# 2_waffling60-SE_matrix.net
KiCad netlist of a schematic drawn in Altium Designer
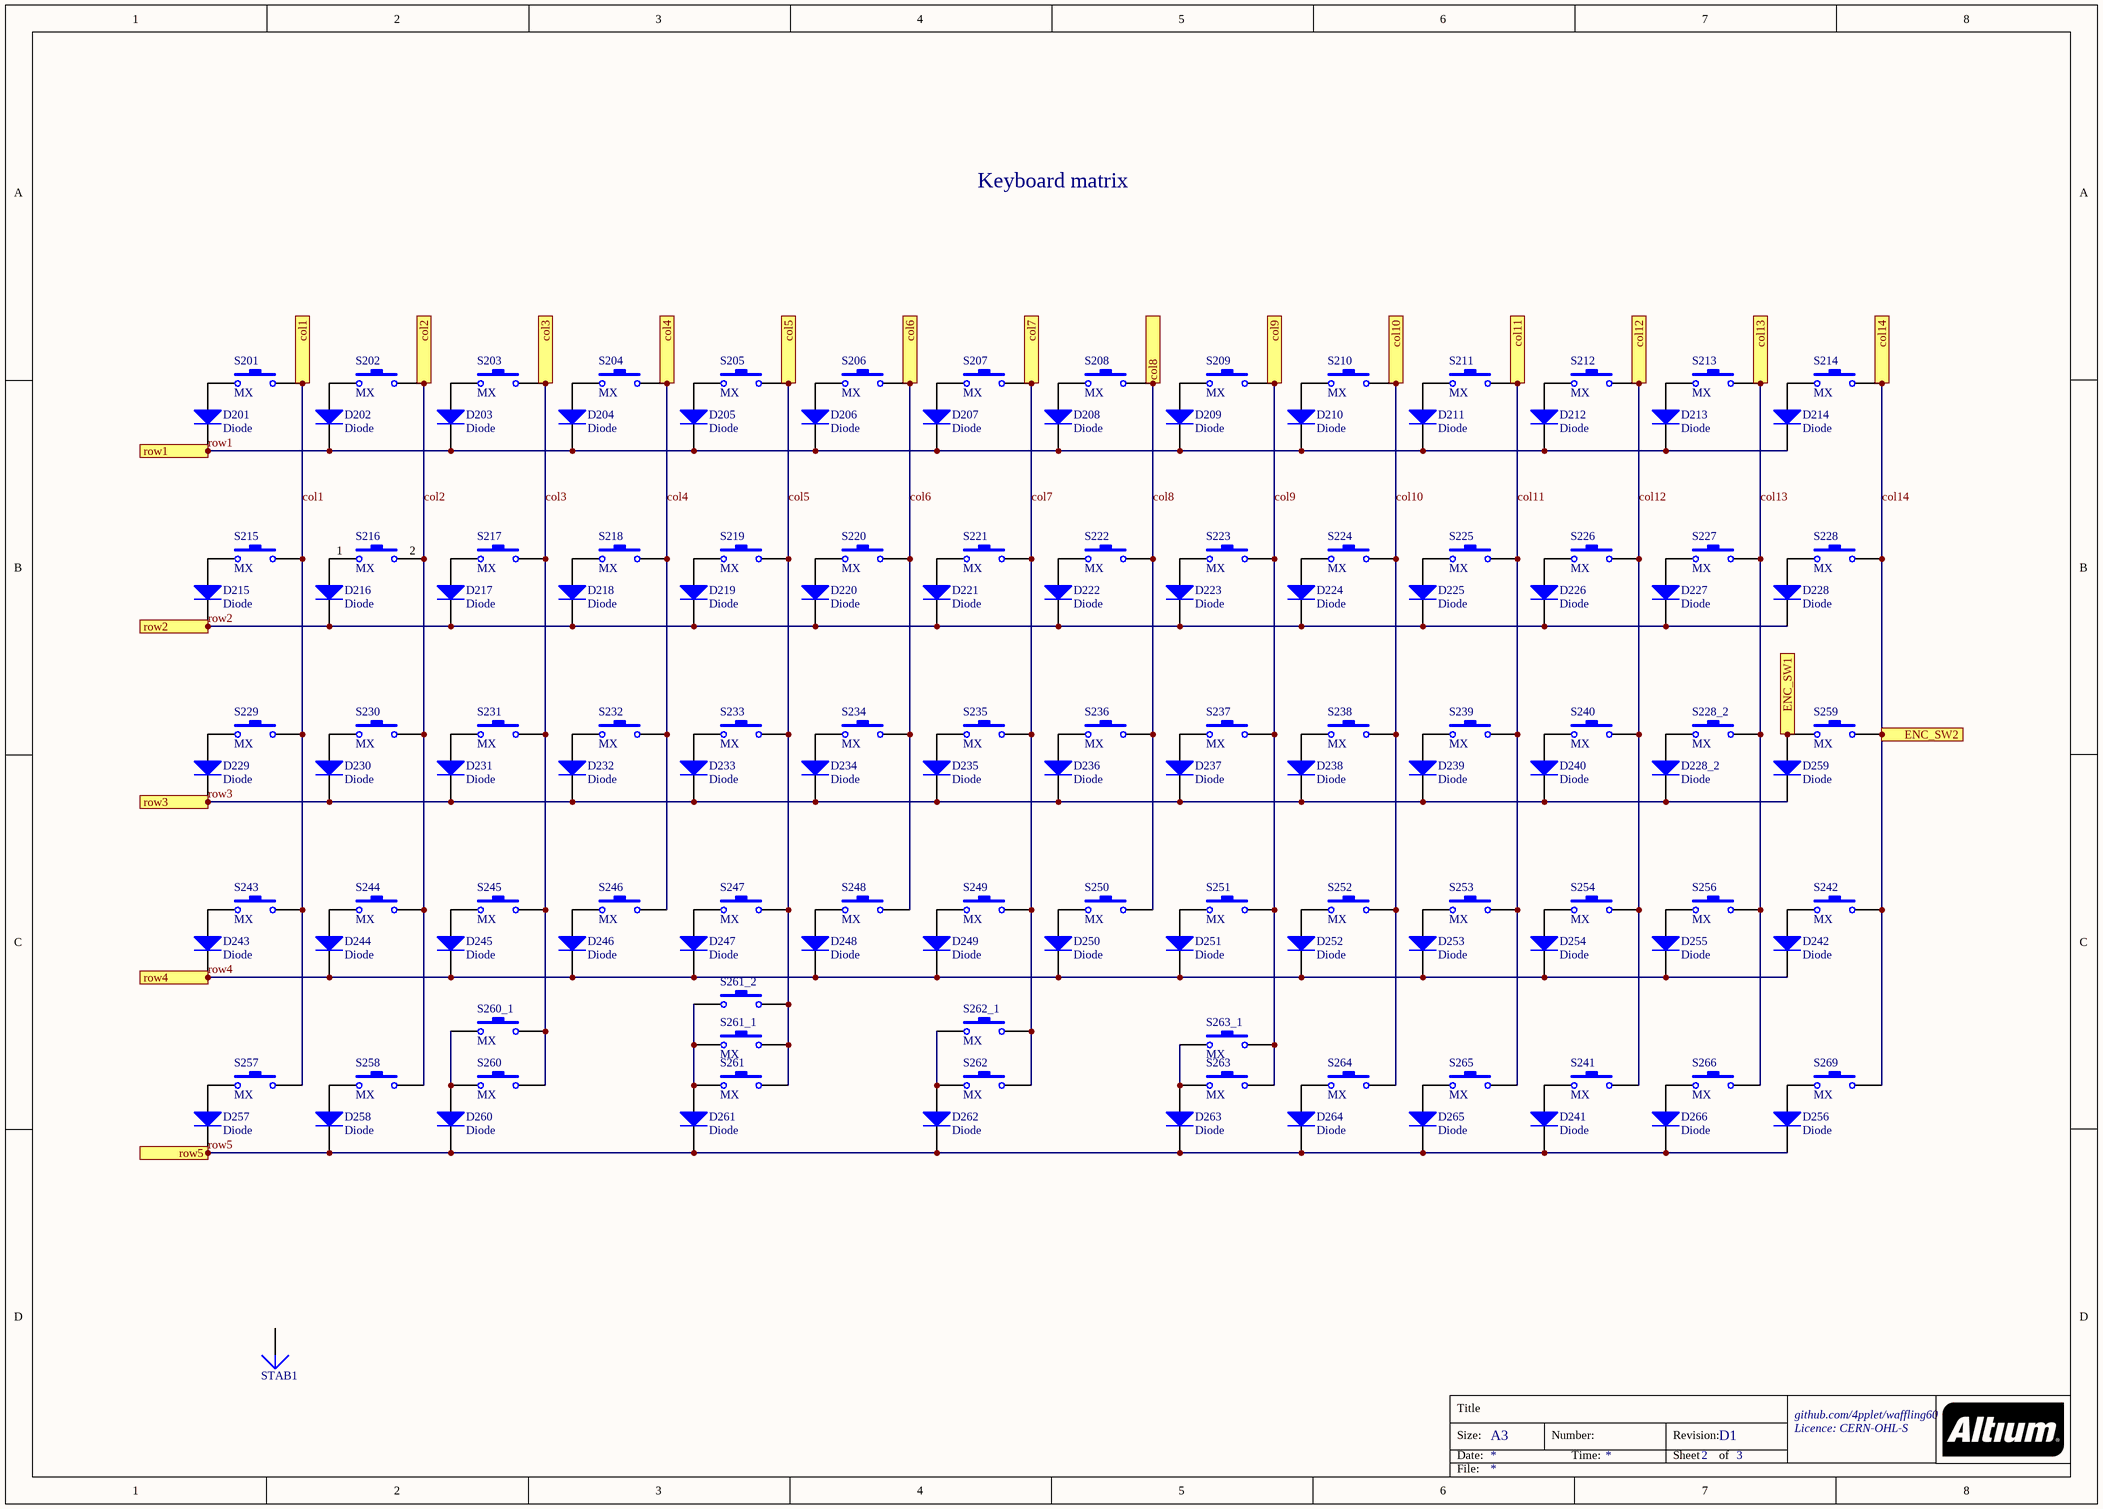
[diagram p0: 2_waffling60-SE_matrix.SchDoc]

(export (version "E")
  (design (tool "Eeschema 10.0.6"))
  (components
    (comp (ref "D201")
      (value "Diode")
      (footprint "SOD-123")
      (description "Default Diode")
      (fields (field (name "LCSC PART #") "C81598") (field (name "MRF.PART") "1N4148W"))
      (libsource (lib "Miscellaneous Devices") (part "Diode"))
    )
    (comp (ref "D202")
      (value "Diode")
      (footprint "SOD-123")
      (description "Default Diode")
      (fields (field (name "LCSC PART #") "C81598") (field (name "MRF.PART") "1N4148W"))
      (libsource (lib "Miscellaneous Devices") (part "Diode"))
    )
    (comp (ref "D203")
      (value "Diode")
      (footprint "SOD-123")
      (description "Default Diode")
      (fields (field (name "LCSC PART #") "C81598") (field (name "MRF.PART") "1N4148W"))
      (libsource (lib "Miscellaneous Devices") (part "Diode"))
    )
    (comp (ref "D204")
      (value "Diode")
      (footprint "SOD-123")
      (description "Default Diode")
      (fields (field (name "LCSC PART #") "C81598") (field (name "MRF.PART") "1N4148W"))
      (libsource (lib "Miscellaneous Devices") (part "Diode"))
    )
    (comp (ref "D205")
      (value "Diode")
      (footprint "SOD-123")
      (description "Default Diode")
      (fields (field (name "LCSC PART #") "C81598") (field (name "MRF.PART") "1N4148W"))
      (libsource (lib "Miscellaneous Devices") (part "Diode"))
    )
    (comp (ref "D206")
      (value "Diode")
      (footprint "SOD-123")
      (description "Default Diode")
      (fields (field (name "LCSC PART #") "C81598") (field (name "MRF.PART") "1N4148W"))
      (libsource (lib "Miscellaneous Devices") (part "Diode"))
    )
    (comp (ref "D207")
      (value "Diode")
      (footprint "SOD-123")
      (description "Default Diode")
      (fields (field (name "LCSC PART #") "C81598") (field (name "MRF.PART") "1N4148W"))
      (libsource (lib "Miscellaneous Devices") (part "Diode"))
    )
    (comp (ref "D208")
      (value "Diode")
      (footprint "SOD-123")
      (description "Default Diode")
      (fields (field (name "LCSC PART #") "C81598") (field (name "MRF.PART") "1N4148W"))
      (libsource (lib "Miscellaneous Devices") (part "Diode"))
    )
    (comp (ref "D209")
      (value "Diode")
      (footprint "SOD-123")
      (description "Default Diode")
      (fields (field (name "LCSC PART #") "C81598") (field (name "MRF.PART") "1N4148W"))
      (libsource (lib "Miscellaneous Devices") (part "Diode"))
    )
    (comp (ref "D210")
      (value "Diode")
      (footprint "SOD-123")
      (description "Default Diode")
      (fields (field (name "LCSC PART #") "C81598") (field (name "MRF.PART") "1N4148W"))
      (libsource (lib "Miscellaneous Devices") (part "Diode"))
    )
    (comp (ref "D211")
      (value "Diode")
      (footprint "SOD-123")
      (description "Default Diode")
      (fields (field (name "LCSC PART #") "C81598") (field (name "MRF.PART") "1N4148W"))
      (libsource (lib "Miscellaneous Devices") (part "Diode"))
    )
    (comp (ref "D212")
      (value "Diode")
      (footprint "SOD-123")
      (description "Default Diode")
      (fields (field (name "LCSC PART #") "C81598") (field (name "MRF.PART") "1N4148W"))
      (libsource (lib "Miscellaneous Devices") (part "Diode"))
    )
    (comp (ref "D213")
      (value "Diode")
      (footprint "SOD-123")
      (description "Default Diode")
      (fields (field (name "LCSC PART #") "C81598") (field (name "MRF.PART") "1N4148W"))
      (libsource (lib "Miscellaneous Devices") (part "Diode"))
    )
    (comp (ref "D214")
      (value "Diode")
      (footprint "SOD-123")
      (description "Default Diode")
      (fields (field (name "LCSC PART #") "C81598") (field (name "MRF.PART") "1N4148W"))
      (libsource (lib "Miscellaneous Devices") (part "Diode"))
    )
    (comp (ref "D215")
      (value "Diode")
      (footprint "SOD-123")
      (description "Default Diode")
      (fields (field (name "LCSC PART #") "C81598") (field (name "MRF.PART") "1N4148W"))
      (libsource (lib "Miscellaneous Devices") (part "Diode"))
    )
    (comp (ref "D216")
      (value "Diode")
      (footprint "SOD-123")
      (description "Default Diode")
      (fields (field (name "LCSC PART #") "C81598") (field (name "MRF.PART") "1N4148W"))
      (libsource (lib "Miscellaneous Devices") (part "Diode"))
    )
    (comp (ref "D217")
      (value "Diode")
      (footprint "SOD-123")
      (description "Default Diode")
      (fields (field (name "LCSC PART #") "C81598") (field (name "MRF.PART") "1N4148W"))
      (libsource (lib "Miscellaneous Devices") (part "Diode"))
    )
    (comp (ref "D218")
      (value "Diode")
      (footprint "SOD-123")
      (description "Default Diode")
      (fields (field (name "LCSC PART #") "C81598") (field (name "MRF.PART") "1N4148W"))
      (libsource (lib "Miscellaneous Devices") (part "Diode"))
    )
    (comp (ref "D219")
      (value "Diode")
      (footprint "SOD-123")
      (description "Default Diode")
      (fields (field (name "LCSC PART #") "C81598") (field (name "MRF.PART") "1N4148W"))
      (libsource (lib "Miscellaneous Devices") (part "Diode"))
    )
    (comp (ref "D220")
      (value "Diode")
      (footprint "SOD-123")
      (description "Default Diode")
      (fields (field (name "LCSC PART #") "C81598") (field (name "MRF.PART") "1N4148W"))
      (libsource (lib "Miscellaneous Devices") (part "Diode"))
    )
    (comp (ref "D221")
      (value "Diode")
      (footprint "SOD-123")
      (description "Default Diode")
      (fields (field (name "LCSC PART #") "C81598") (field (name "MRF.PART") "1N4148W"))
      (libsource (lib "Miscellaneous Devices") (part "Diode"))
    )
    (comp (ref "D222")
      (value "Diode")
      (footprint "SOD-123")
      (description "Default Diode")
      (fields (field (name "LCSC PART #") "C81598") (field (name "MRF.PART") "1N4148W"))
      (libsource (lib "Miscellaneous Devices") (part "Diode"))
    )
    (comp (ref "D223")
      (value "Diode")
      (footprint "SOD-123")
      (description "Default Diode")
      (fields (field (name "LCSC PART #") "C81598") (field (name "MRF.PART") "1N4148W"))
      (libsource (lib "Miscellaneous Devices") (part "Diode"))
    )
    (comp (ref "D224")
      (value "Diode")
      (footprint "SOD-123")
      (description "Default Diode")
      (fields (field (name "LCSC PART #") "C81598") (field (name "MRF.PART") "1N4148W"))
      (libsource (lib "Miscellaneous Devices") (part "Diode"))
    )
    (comp (ref "D225")
      (value "Diode")
      (footprint "SOD-123")
      (description "Default Diode")
      (fields (field (name "LCSC PART #") "C81598") (field (name "MRF.PART") "1N4148W"))
      (libsource (lib "Miscellaneous Devices") (part "Diode"))
    )
    (comp (ref "D226")
      (value "Diode")
      (footprint "SOD-123")
      (description "Default Diode")
      (fields (field (name "LCSC PART #") "C81598") (field (name "MRF.PART") "1N4148W"))
      (libsource (lib "Miscellaneous Devices") (part "Diode"))
    )
    (comp (ref "D227")
      (value "Diode")
      (footprint "SOD-123")
      (description "Default Diode")
      (fields (field (name "LCSC PART #") "C81598") (field (name "MRF.PART") "1N4148W"))
      (libsource (lib "Miscellaneous Devices") (part "Diode"))
    )
    (comp (ref "D228")
      (value "Diode")
      (footprint "SOD-123")
      (description "Default Diode")
      (fields (field (name "LCSC PART #") "C81598") (field (name "MRF.PART") "1N4148W"))
      (libsource (lib "Miscellaneous Devices") (part "Diode"))
    )
    (comp (ref "D228_2")
      (value "Diode")
      (footprint "SOD-123")
      (description "Default Diode")
      (fields (field (name "LCSC PART #") "C81598") (field (name "MRF.PART") "1N4148W"))
      (libsource (lib "Miscellaneous Devices") (part "Diode"))
    )
    (comp (ref "D229")
      (value "Diode")
      (footprint "SOD-123")
      (description "Default Diode")
      (fields (field (name "LCSC PART #") "C81598") (field (name "MRF.PART") "1N4148W"))
      (libsource (lib "Miscellaneous Devices") (part "Diode"))
    )
    (comp (ref "D230")
      (value "Diode")
      (footprint "SOD-123")
      (description "Default Diode")
      (fields (field (name "LCSC PART #") "C81598") (field (name "MRF.PART") "1N4148W"))
      (libsource (lib "Miscellaneous Devices") (part "Diode"))
    )
    (comp (ref "D231")
      (value "Diode")
      (footprint "SOD-123")
      (description "Default Diode")
      (fields (field (name "LCSC PART #") "C81598") (field (name "MRF.PART") "1N4148W"))
      (libsource (lib "Miscellaneous Devices") (part "Diode"))
    )
    (comp (ref "D232")
      (value "Diode")
      (footprint "SOD-123")
      (description "Default Diode")
      (fields (field (name "LCSC PART #") "C81598") (field (name "MRF.PART") "1N4148W"))
      (libsource (lib "Miscellaneous Devices") (part "Diode"))
    )
    (comp (ref "D233")
      (value "Diode")
      (footprint "SOD-123")
      (description "Default Diode")
      (fields (field (name "LCSC PART #") "C81598") (field (name "MRF.PART") "1N4148W"))
      (libsource (lib "Miscellaneous Devices") (part "Diode"))
    )
    (comp (ref "D234")
      (value "Diode")
      (footprint "SOD-123")
      (description "Default Diode")
      (fields (field (name "LCSC PART #") "C81598") (field (name "MRF.PART") "1N4148W"))
      (libsource (lib "Miscellaneous Devices") (part "Diode"))
    )
    (comp (ref "D235")
      (value "Diode")
      (footprint "SOD-123")
      (description "Default Diode")
      (fields (field (name "LCSC PART #") "C81598") (field (name "MRF.PART") "1N4148W"))
      (libsource (lib "Miscellaneous Devices") (part "Diode"))
    )
    (comp (ref "D236")
      (value "Diode")
      (footprint "SOD-123")
      (description "Default Diode")
      (fields (field (name "LCSC PART #") "C81598") (field (name "MRF.PART") "1N4148W"))
      (libsource (lib "Miscellaneous Devices") (part "Diode"))
    )
    (comp (ref "D237")
      (value "Diode")
      (footprint "SOD-123")
      (description "Default Diode")
      (fields (field (name "LCSC PART #") "C81598") (field (name "MRF.PART") "1N4148W"))
      (libsource (lib "Miscellaneous Devices") (part "Diode"))
    )
    (comp (ref "D238")
      (value "Diode")
      (footprint "SOD-123")
      (description "Default Diode")
      (fields (field (name "LCSC PART #") "C81598") (field (name "MRF.PART") "1N4148W"))
      (libsource (lib "Miscellaneous Devices") (part "Diode"))
    )
    (comp (ref "D239")
      (value "Diode")
      (footprint "SOD-123")
      (description "Default Diode")
      (fields (field (name "LCSC PART #") "C81598") (field (name "MRF.PART") "1N4148W"))
      (libsource (lib "Miscellaneous Devices") (part "Diode"))
    )
    (comp (ref "D240")
      (value "Diode")
      (footprint "SOD-123")
      (description "Default Diode")
      (fields (field (name "LCSC PART #") "C81598") (field (name "MRF.PART") "1N4148W"))
      (libsource (lib "Miscellaneous Devices") (part "Diode"))
    )
    (comp (ref "D241")
      (value "Diode")
      (footprint "SOD-123")
      (description "Default Diode")
      (fields (field (name "LCSC PART #") "C81598") (field (name "MRF.PART") "1N4148W"))
      (libsource (lib "Miscellaneous Devices") (part "Diode"))
    )
    (comp (ref "D242")
      (value "Diode")
      (footprint "SOD-123")
      (description "Default Diode")
      (fields (field (name "LCSC PART #") "C81598") (field (name "MRF.PART") "1N4148W"))
      (libsource (lib "Miscellaneous Devices") (part "Diode"))
    )
    (comp (ref "D243")
      (value "Diode")
      (footprint "SOD-123")
      (description "Default Diode")
      (fields (field (name "LCSC PART #") "C81598") (field (name "MRF.PART") "1N4148W"))
      (libsource (lib "Miscellaneous Devices") (part "Diode"))
    )
    (comp (ref "D244")
      (value "Diode")
      (footprint "SOD-123")
      (description "Default Diode")
      (fields (field (name "LCSC PART #") "C81598") (field (name "MRF.PART") "1N4148W"))
      (libsource (lib "Miscellaneous Devices") (part "Diode"))
    )
    (comp (ref "D245")
      (value "Diode")
      (footprint "SOD-123")
      (description "Default Diode")
      (fields (field (name "LCSC PART #") "C81598") (field (name "MRF.PART") "1N4148W"))
      (libsource (lib "Miscellaneous Devices") (part "Diode"))
    )
    (comp (ref "D246")
      (value "Diode")
      (footprint "SOD-123")
      (description "Default Diode")
      (fields (field (name "LCSC PART #") "C81598") (field (name "MRF.PART") "1N4148W"))
      (libsource (lib "Miscellaneous Devices") (part "Diode"))
    )
    (comp (ref "D247")
      (value "Diode")
      (footprint "SOD-123")
      (description "Default Diode")
      (fields (field (name "LCSC PART #") "C81598") (field (name "MRF.PART") "1N4148W"))
      (libsource (lib "Miscellaneous Devices") (part "Diode"))
    )
    (comp (ref "D248")
      (value "Diode")
      (footprint "SOD-123")
      (description "Default Diode")
      (fields (field (name "LCSC PART #") "C81598") (field (name "MRF.PART") "1N4148W"))
      (libsource (lib "Miscellaneous Devices") (part "Diode"))
    )
    (comp (ref "D249")
      (value "Diode")
      (footprint "SOD-123")
      (description "Default Diode")
      (fields (field (name "LCSC PART #") "C81598") (field (name "MRF.PART") "1N4148W"))
      (libsource (lib "Miscellaneous Devices") (part "Diode"))
    )
    (comp (ref "D250")
      (value "Diode")
      (footprint "SOD-123")
      (description "Default Diode")
      (fields (field (name "LCSC PART #") "C81598") (field (name "MRF.PART") "1N4148W"))
      (libsource (lib "Miscellaneous Devices") (part "Diode"))
    )
    (comp (ref "D251")
      (value "Diode")
      (footprint "SOD-123")
      (description "Default Diode")
      (fields (field (name "LCSC PART #") "C81598") (field (name "MRF.PART") "1N4148W"))
      (libsource (lib "Miscellaneous Devices") (part "Diode"))
    )
    (comp (ref "D252")
      (value "Diode")
      (footprint "SOD-123")
      (description "Default Diode")
      (fields (field (name "LCSC PART #") "C81598") (field (name "MRF.PART") "1N4148W"))
      (libsource (lib "Miscellaneous Devices") (part "Diode"))
    )
    (comp (ref "D253")
      (value "Diode")
      (footprint "SOD-123")
      (description "Default Diode")
      (fields (field (name "LCSC PART #") "C81598") (field (name "MRF.PART") "1N4148W"))
      (libsource (lib "Miscellaneous Devices") (part "Diode"))
    )
    (comp (ref "D254")
      (value "Diode")
      (footprint "SOD-123")
      (description "Default Diode")
      (fields (field (name "LCSC PART #") "C81598") (field (name "MRF.PART") "1N4148W"))
      (libsource (lib "Miscellaneous Devices") (part "Diode"))
    )
    (comp (ref "D255")
      (value "Diode")
      (footprint "SOD-123")
      (description "Default Diode")
      (fields (field (name "LCSC PART #") "C81598") (field (name "MRF.PART") "1N4148W"))
      (libsource (lib "Miscellaneous Devices") (part "Diode"))
    )
    (comp (ref "D256")
      (value "Diode")
      (footprint "SOD-123")
      (description "Default Diode")
      (fields (field (name "LCSC PART #") "C81598") (field (name "MRF.PART") "1N4148W"))
      (libsource (lib "Miscellaneous Devices") (part "Diode"))
    )
    (comp (ref "D257")
      (value "Diode")
      (footprint "SOD-123")
      (description "Default Diode")
      (fields (field (name "LCSC PART #") "C81598") (field (name "MRF.PART") "1N4148W"))
      (libsource (lib "Miscellaneous Devices") (part "Diode"))
    )
    (comp (ref "D258")
      (value "Diode")
      (footprint "SOD-123")
      (description "Default Diode")
      (fields (field (name "LCSC PART #") "C81598") (field (name "MRF.PART") "1N4148W"))
      (libsource (lib "Miscellaneous Devices") (part "Diode"))
    )
    (comp (ref "D259")
      (value "Diode")
      (footprint "SOD-123")
      (description "Default Diode")
      (fields (field (name "LCSC PART #") "C81598") (field (name "MRF.PART") "1N4148W"))
      (libsource (lib "Miscellaneous Devices") (part "Diode"))
    )
    (comp (ref "D260")
      (value "Diode")
      (footprint "SOD-123")
      (description "Default Diode")
      (fields (field (name "LCSC PART #") "C81598") (field (name "MRF.PART") "1N4148W"))
      (libsource (lib "Miscellaneous Devices") (part "Diode"))
    )
    (comp (ref "D261")
      (value "Diode")
      (footprint "SOD-123")
      (description "Default Diode")
      (fields (field (name "LCSC PART #") "C81598") (field (name "MRF.PART") "1N4148W"))
      (libsource (lib "Miscellaneous Devices") (part "Diode"))
    )
    (comp (ref "D262")
      (value "Diode")
      (footprint "SOD-123")
      (description "Default Diode")
      (fields (field (name "LCSC PART #") "C81598") (field (name "MRF.PART") "1N4148W"))
      (libsource (lib "Miscellaneous Devices") (part "Diode"))
    )
    (comp (ref "D263")
      (value "Diode")
      (footprint "SOD-123")
      (description "Default Diode")
      (fields (field (name "LCSC PART #") "C81598") (field (name "MRF.PART") "1N4148W"))
      (libsource (lib "Miscellaneous Devices") (part "Diode"))
    )
    (comp (ref "D264")
      (value "Diode")
      (footprint "SOD-123")
      (description "Default Diode")
      (fields (field (name "LCSC PART #") "C81598") (field (name "MRF.PART") "1N4148W"))
      (libsource (lib "Miscellaneous Devices") (part "Diode"))
    )
    (comp (ref "D265")
      (value "Diode")
      (footprint "SOD-123")
      (description "Default Diode")
      (fields (field (name "LCSC PART #") "C81598") (field (name "MRF.PART") "1N4148W"))
      (libsource (lib "Miscellaneous Devices") (part "Diode"))
    )
    (comp (ref "D266")
      (value "Diode")
      (footprint "SOD-123")
      (description "Default Diode")
      (fields (field (name "LCSC PART #") "C81598") (field (name "MRF.PART") "1N4148W"))
      (libsource (lib "Miscellaneous Devices") (part "Diode"))
    )
    (comp (ref "S201")
      (value "MX")
      (footprint "MX-switch - switched pol")
      (description "Switch")
      (libsource (lib "Miscellaneous Devices") (part "SW-PB"))
    )
    (comp (ref "S202")
      (value "MX")
      (footprint "MX-switch")
      (description "Switch")
      (libsource (lib "Miscellaneous Devices") (part "SW-PB"))
    )
    (comp (ref "S203")
      (value "MX")
      (footprint "MX-switch - switched pol")
      (description "Switch")
      (libsource (lib "Miscellaneous Devices") (part "SW-PB"))
    )
    (comp (ref "S204")
      (value "MX")
      (footprint "MX-switch - switched pol")
      (description "Switch")
      (libsource (lib "Miscellaneous Devices") (part "SW-PB"))
    )
    (comp (ref "S205")
      (value "MX")
      (footprint "MX-switch - switched pol")
      (description "Switch")
      (libsource (lib "Miscellaneous Devices") (part "SW-PB"))
    )
    (comp (ref "S206")
      (value "MX")
      (footprint "MX-switch - switched pol")
      (description "Switch")
      (libsource (lib "Miscellaneous Devices") (part "SW-PB"))
    )
    (comp (ref "S207")
      (value "MX")
      (footprint "MX-switch - switched pol")
      (description "Switch")
      (libsource (lib "Miscellaneous Devices") (part "SW-PB"))
    )
    (comp (ref "S208")
      (value "MX")
      (footprint "MX-switch - switched pol")
      (description "Switch")
      (libsource (lib "Miscellaneous Devices") (part "SW-PB"))
    )
    (comp (ref "S209")
      (value "MX")
      (footprint "MX-switch - switched pol")
      (description "Switch")
      (libsource (lib "Miscellaneous Devices") (part "SW-PB"))
    )
    (comp (ref "S210")
      (value "MX")
      (footprint "MX-switch - switched pol")
      (description "Switch")
      (libsource (lib "Miscellaneous Devices") (part "SW-PB"))
    )
    (comp (ref "S211")
      (value "MX")
      (footprint "MX-switch - switched pol")
      (description "Switch")
      (libsource (lib "Miscellaneous Devices") (part "SW-PB"))
    )
    (comp (ref "S212")
      (value "MX")
      (footprint "MX-switch - switched pol")
      (description "Switch")
      (libsource (lib "Miscellaneous Devices") (part "SW-PB"))
    )
    (comp (ref "S213")
      (value "MX")
      (footprint "MX-switch - switched pol")
      (description "Switch")
      (libsource (lib "Miscellaneous Devices") (part "SW-PB"))
    )
    (comp (ref "S214")
      (value "MX")
      (footprint "MX-switch")
      (description "Switch")
      (libsource (lib "Miscellaneous Devices") (part "SW-PB"))
    )
    (comp (ref "S215")
      (value "MX")
      (footprint "MX-switch - switched pol")
      (description "TAB")
      (libsource (lib "Miscellaneous Devices") (part "SW-PB"))
    )
    (comp (ref "S216")
      (value "MX")
      (footprint "MX-switch")
      (description "Switch")
      (libsource (lib "") (part "SW-PB_1"))
    )
    (comp (ref "S217")
      (value "MX")
      (footprint "MX-switch - switched pol")
      (description "Switch")
      (libsource (lib "Miscellaneous Devices") (part "SW-PB"))
    )
    (comp (ref "S218")
      (value "MX")
      (footprint "MX-switch - switched pol")
      (description "Switch")
      (libsource (lib "Miscellaneous Devices") (part "SW-PB"))
    )
    (comp (ref "S219")
      (value "MX")
      (footprint "MX-switch - switched pol")
      (description "Switch")
      (libsource (lib "Miscellaneous Devices") (part "SW-PB"))
    )
    (comp (ref "S220")
      (value "MX")
      (footprint "MX-switch")
      (description "Switch")
      (libsource (lib "Miscellaneous Devices") (part "SW-PB"))
    )
    (comp (ref "S221")
      (value "MX")
      (footprint "MX-switch - switched pol")
      (description "Switch")
      (libsource (lib "Miscellaneous Devices") (part "SW-PB"))
    )
    (comp (ref "S222")
      (value "MX")
      (footprint "MX-switch - switched pol")
      (description "Switch")
      (libsource (lib "Miscellaneous Devices") (part "SW-PB"))
    )
    (comp (ref "S223")
      (value "MX")
      (footprint "MX-switch - switched pol")
      (description "Switch")
      (libsource (lib "Miscellaneous Devices") (part "SW-PB"))
    )
    (comp (ref "S224")
      (value "MX")
      (footprint "MX-switch - switched pol")
      (description "Switch")
      (libsource (lib "Miscellaneous Devices") (part "SW-PB"))
    )
    (comp (ref "S225")
      (value "MX")
      (footprint "MX-switch - switched pol")
      (description "Switch")
      (libsource (lib "Miscellaneous Devices") (part "SW-PB"))
    )
    (comp (ref "S226")
      (value "MX")
      (footprint "MX-switch")
      (description "Switch")
      (libsource (lib "Miscellaneous Devices") (part "SW-PB"))
    )
    (comp (ref "S227")
      (value "MX")
      (footprint "MX-switch")
      (description "Switch")
      (libsource (lib "Miscellaneous Devices") (part "SW-PB"))
    )
    (comp (ref "S228")
      (value "MX")
      (footprint "MX-switch - 1.5U")
      (description "Switch")
      (libsource (lib "Miscellaneous Devices") (part "SW-PB"))
    )
    (comp (ref "S228_2")
      (value "MX")
      (footprint "MX-switch")
      (description "Switch")
      (libsource (lib "Miscellaneous Devices") (part "SW-PB"))
    )
    (comp (ref "S229")
      (value "MX")
      (footprint "MX-switch - CAPS")
      (description "Switch")
      (libsource (lib "Miscellaneous Devices") (part "SW-PB"))
    )
    (comp (ref "S230")
      (value "MX")
      (footprint "MX-switch")
      (description "Switch")
      (libsource (lib "Miscellaneous Devices") (part "SW-PB"))
    )
    (comp (ref "S231")
      (value "MX")
      (footprint "MX-switch - switched pol")
      (description "Switch")
      (libsource (lib "Miscellaneous Devices") (part "SW-PB"))
    )
    (comp (ref "S232")
      (value "MX")
      (footprint "MX-switch - switched pol")
      (description "Switch")
      (libsource (lib "Miscellaneous Devices") (part "SW-PB"))
    )
    (comp (ref "S233")
      (value "MX")
      (footprint "MX-switch - switched pol")
      (description "Switch")
      (libsource (lib "Miscellaneous Devices") (part "SW-PB"))
    )
    (comp (ref "S234")
      (value "MX")
      (footprint "MX-switch - switched pol")
      (description "Switch")
      (libsource (lib "Miscellaneous Devices") (part "SW-PB"))
    )
    (comp (ref "S235")
      (value "MX")
      (footprint "MX-switch - switched pol")
      (description "Switch")
      (libsource (lib "Miscellaneous Devices") (part "SW-PB"))
    )
    (comp (ref "S236")
      (value "MX")
      (footprint "MX-switch - switched pol")
      (description "Switch")
      (libsource (lib "Miscellaneous Devices") (part "SW-PB"))
    )
    (comp (ref "S237")
      (value "MX")
      (footprint "MX-switch - switched pol")
      (description "Switch")
      (libsource (lib "Miscellaneous Devices") (part "SW-PB"))
    )
    (comp (ref "S238")
      (value "MX")
      (footprint "MX-switch - switched pol")
      (description "Switch")
      (libsource (lib "Miscellaneous Devices") (part "SW-PB"))
    )
    (comp (ref "S239")
      (value "MX")
      (footprint "MX-switch - switched pol")
      (description "Switch")
      (libsource (lib "Miscellaneous Devices") (part "SW-PB"))
    )
    (comp (ref "S240")
      (value "MX")
      (footprint "MX-switch - switched pol")
      (description "Switch")
      (libsource (lib "Miscellaneous Devices") (part "SW-PB"))
    )
    (comp (ref "S241")
      (value "MX")
      (footprint "MX-switch - 1u MOD-R")
      (description "Switch")
      (libsource (lib "Miscellaneous Devices") (part "SW-PB"))
    )
    (comp (ref "S242")
      (value "MX")
      (footprint "MX-switch - Enter - Rotated Stab")
      (description "Switch")
      (libsource (lib "Miscellaneous Devices") (part "SW-PB"))
    )
    (comp (ref "S243")
      (value "MX")
      (footprint "MX-switch - Left shift")
      (description "Switch")
      (libsource (lib "Miscellaneous Devices") (part "SW-PB"))
    )
    (comp (ref "S244")
      (value "MX")
      (footprint "MX-switch")
      (description "Switch")
      (libsource (lib "Miscellaneous Devices") (part "SW-PB"))
    )
    (comp (ref "S245")
      (value "MX")
      (footprint "MX-switch - switched pol")
      (description "Switch")
      (libsource (lib "Miscellaneous Devices") (part "SW-PB"))
    )
    (comp (ref "S246")
      (value "MX")
      (footprint "MX-switch - switched pol")
      (description "Switch")
      (libsource (lib "Miscellaneous Devices") (part "SW-PB"))
    )
    (comp (ref "S247")
      (value "MX")
      (footprint "MX-switch - switched pol")
      (description "Switch")
      (libsource (lib "Miscellaneous Devices") (part "SW-PB"))
    )
    (comp (ref "S248")
      (value "MX")
      (footprint "MX-switch - switched pol")
      (description "Switch")
      (libsource (lib "Miscellaneous Devices") (part "SW-PB"))
    )
    (comp (ref "S249")
      (value "MX")
      (footprint "MX-switch - switched pol")
      (description "Switch")
      (libsource (lib "Miscellaneous Devices") (part "SW-PB"))
    )
    (comp (ref "S250")
      (value "MX")
      (footprint "MX-switch - switched pol")
      (description "Switch")
      (libsource (lib "Miscellaneous Devices") (part "SW-PB"))
    )
    (comp (ref "S251")
      (value "MX")
      (footprint "MX-switch - switched pol")
      (description "Switch")
      (libsource (lib "Miscellaneous Devices") (part "SW-PB"))
    )
    (comp (ref "S252")
      (value "MX")
      (footprint "MX-switch - switched pol")
      (description "Switch")
      (libsource (lib "Miscellaneous Devices") (part "SW-PB"))
    )
    (comp (ref "S253")
      (value "MX")
      (footprint "MX-switch - switched pol")
      (description "Switch")
      (libsource (lib "Miscellaneous Devices") (part "SW-PB"))
    )
    (comp (ref "S254")
      (value "MX")
      (footprint "MX-switch - switched pol")
      (description "Switch")
      (libsource (lib "Miscellaneous Devices") (part "SW-PB"))
    )
    (comp (ref "S256")
      (value "MX")
      (footprint "MX-switch - right shift")
      (description "Switch")
      (libsource (lib "Miscellaneous Devices") (part "SW-PB"))
    )
    (comp (ref "S257")
      (value "MX")
      (footprint "MX-switch - 1.5u MOD-L")
      (description "Switch")
      (libsource (lib "Miscellaneous Devices") (part "SW-PB"))
    )
    (comp (ref "S258")
      (value "MX")
      (footprint "MX-switch - 1u MOD-L")
      (description "Switch")
      (libsource (lib "Miscellaneous Devices") (part "SW-PB"))
    )
    (comp (ref "S259")
      (value "MX")
      (footprint "MX-switch - backspace")
      (description "Switch")
      (libsource (lib "Miscellaneous Devices") (part "SW-PB"))
    )
    (comp (ref "S260")
      (value "MX")
      (footprint "MX-switch - 1.5u MOD-L")
      (description "Switch")
      (libsource (lib "Miscellaneous Devices") (part "SW-PB"))
    )
    (comp (ref "S260_1")
      (value "MX")
      (footprint "MX-switch")
      (description "Switch")
      (libsource (lib "Miscellaneous Devices") (part "SW-PB"))
    )
    (comp (ref "S261")
      (value "MX")
      (footprint "MX-SWITCH - L SPLIT SPACE_V2")
      (description "Switch")
      (libsource (lib "Miscellaneous Devices") (part "SW-PB"))
    )
    (comp (ref "S261_1")
      (value "MX")
      (footprint "MX-switch - 3U - rotated stab")
      (description "Switch")
      (libsource (lib "Miscellaneous Devices") (part "SW-PB"))
    )
    (comp (ref "S261_2")
      (value "Comment")
      (footprint "MX-switch")
      (description "Switch")
      (libsource (lib "") (part "SW-PB_2"))
    )
    (comp (ref "S262")
      (value "MX")
      (footprint "MX-switch - Space_V3")
      (description "Switch")
      (libsource (lib "Miscellaneous Devices") (part "SW-PB"))
    )
    (comp (ref "S262_1")
      (value "MX")
      (footprint "MX-switch - switched pol")
      (description "Switch")
      (libsource (lib "Miscellaneous Devices") (part "SW-PB"))
    )
    (comp (ref "S263")
      (value "MX")
      (footprint "MX-SWITCH - R SPLIT SPACE_V2")
      (description "Switch")
      (libsource (lib "Miscellaneous Devices") (part "SW-PB"))
    )
    (comp (ref "S263_1")
      (value "MX")
      (footprint "MX-switch - 3U - rotated stab")
      (description "Switch")
      (libsource (lib "Miscellaneous Devices") (part "SW-PB"))
    )
    (comp (ref "S264")
      (value "MX")
      (footprint "MX-switch - switched pol")
      (description "Switch")
      (libsource (lib "Miscellaneous Devices") (part "SW-PB"))
    )
    (comp (ref "S265")
      (value "MX")
      (footprint "MX-switch - 1.5u MOD-R")
      (description "Switch")
      (libsource (lib "Miscellaneous Devices") (part "SW-PB"))
    )
    (comp (ref "S266")
      (value "MX")
      (footprint "MX-switch - 1.5u MOD-R")
      (description "Switch")
      (libsource (lib "Miscellaneous Devices") (part "SW-PB"))
    )
    (comp (ref "S269")
      (value "MX")
      (footprint "MX-switch")
      (description "Switch")
      (libsource (lib "Miscellaneous Devices") (part "SW-PB"))
    )
    (comp (ref "STAB1")
      (value "Plug")
      (footprint "Stab 10U")
      (libsource (lib "Miscellaneous Connectors") (part "Plug"))
    )
  )
  (nets
    (net (code "1") (name "/ENC_SW1") (class "Default")
      (node (ref "D259") (pin "1") (pinfunction "A_1") (pintype "passive"))
      (node (ref "S259") (pin "1") (pinfunction "1_1") (pintype "passive"))
    )
    (net (code "2") (name "/col1") (class "Default")
      (node (ref "S201") (pin "2") (pinfunction "2_2") (pintype "passive"))
      (node (ref "S215") (pin "2") (pinfunction "2_2") (pintype "passive"))
      (node (ref "S229") (pin "1") (pinfunction "1_1") (pintype "passive"))
      (node (ref "S243") (pin "2") (pinfunction "2_2") (pintype "passive"))
      (node (ref "S257") (pin "1") (pinfunction "1_1") (pintype "passive"))
    )
    (net (code "3") (name "/col2") (class "Default")
      (node (ref "S202") (pin "2") (pinfunction "2_2") (pintype "passive"))
      (node (ref "S216") (pin "2") (pinfunction "2_2") (pintype "passive"))
      (node (ref "S230") (pin "2") (pinfunction "2_2") (pintype "passive"))
      (node (ref "S244") (pin "1") (pinfunction "1_1") (pintype "passive"))
      (node (ref "S258") (pin "2") (pinfunction "2_2") (pintype "passive"))
    )
    (net (code "4") (name "/col3") (class "Default")
      (node (ref "S203") (pin "2") (pinfunction "2_2") (pintype "passive"))
      (node (ref "S217") (pin "2") (pinfunction "2_2") (pintype "passive"))
      (node (ref "S231") (pin "2") (pinfunction "2_2") (pintype "passive"))
      (node (ref "S245") (pin "2") (pinfunction "2_2") (pintype "passive"))
      (node (ref "S260") (pin "2") (pinfunction "2_2") (pintype "passive"))
      (node (ref "S260_1") (pin "2") (pinfunction "2_2") (pintype "passive"))
    )
    (net (code "5") (name "/col4") (class "Default")
      (node (ref "S204") (pin "2") (pinfunction "2_2") (pintype "passive"))
      (node (ref "S218") (pin "2") (pinfunction "2_2") (pintype "passive"))
      (node (ref "S232") (pin "2") (pinfunction "2_2") (pintype "passive"))
      (node (ref "S246") (pin "2") (pinfunction "2_2") (pintype "passive"))
    )
    (net (code "6") (name "/col5") (class "Default")
      (node (ref "S205") (pin "2") (pinfunction "2_2") (pintype "passive"))
      (node (ref "S219") (pin "2") (pinfunction "2_2") (pintype "passive"))
      (node (ref "S233") (pin "2") (pinfunction "2_2") (pintype "passive"))
      (node (ref "S247") (pin "2") (pinfunction "2_2") (pintype "passive"))
      (node (ref "S261") (pin "2") (pinfunction "2_2") (pintype "passive"))
      (node (ref "S261_1") (pin "2") (pinfunction "2_2") (pintype "passive"))
      (node (ref "S261_2") (pin "1") (pinfunction "1_1") (pintype "passive"))
    )
    (net (code "7") (name "/col6") (class "Default")
      (node (ref "S206") (pin "2") (pinfunction "2_2") (pintype "passive"))
      (node (ref "S220") (pin "2") (pinfunction "2_2") (pintype "passive"))
      (node (ref "S234") (pin "2") (pinfunction "2_2") (pintype "passive"))
      (node (ref "S248") (pin "2") (pinfunction "2_2") (pintype "passive"))
    )
    (net (code "8") (name "/col7") (class "Default")
      (node (ref "S207") (pin "2") (pinfunction "2_2") (pintype "passive"))
      (node (ref "S221") (pin "2") (pinfunction "2_2") (pintype "passive"))
      (node (ref "S235") (pin "2") (pinfunction "2_2") (pintype "passive"))
      (node (ref "S249") (pin "2") (pinfunction "2_2") (pintype "passive"))
      (node (ref "S262") (pin "1") (pinfunction "1_1") (pintype "passive"))
      (node (ref "S262_1") (pin "1") (pinfunction "1_1") (pintype "passive"))
    )
    (net (code "9") (name "/col8") (class "Default")
      (node (ref "S208") (pin "2") (pinfunction "2_2") (pintype "passive"))
      (node (ref "S222") (pin "2") (pinfunction "2_2") (pintype "passive"))
      (node (ref "S236") (pin "2") (pinfunction "2_2") (pintype "passive"))
      (node (ref "S250") (pin "2") (pinfunction "2_2") (pintype "passive"))
    )
    (net (code "10") (name "/col9") (class "Default")
      (node (ref "S209") (pin "2") (pinfunction "2_2") (pintype "passive"))
      (node (ref "S223") (pin "2") (pinfunction "2_2") (pintype "passive"))
      (node (ref "S237") (pin "2") (pinfunction "2_2") (pintype "passive"))
      (node (ref "S251") (pin "2") (pinfunction "2_2") (pintype "passive"))
      (node (ref "S263") (pin "1") (pinfunction "1_1") (pintype "passive"))
      (node (ref "S263_1") (pin "1") (pinfunction "1_1") (pintype "passive"))
    )
    (net (code "11") (name "/col10") (class "Default")
      (node (ref "S210") (pin "2") (pinfunction "2_2") (pintype "passive"))
      (node (ref "S224") (pin "2") (pinfunction "2_2") (pintype "passive"))
      (node (ref "S238") (pin "2") (pinfunction "2_2") (pintype "passive"))
      (node (ref "S252") (pin "2") (pinfunction "2_2") (pintype "passive"))
      (node (ref "S264") (pin "2") (pinfunction "2_2") (pintype "passive"))
    )
    (net (code "12") (name "/col11") (class "Default")
      (node (ref "S211") (pin "2") (pinfunction "2_2") (pintype "passive"))
      (node (ref "S225") (pin "2") (pinfunction "2_2") (pintype "passive"))
      (node (ref "S239") (pin "2") (pinfunction "2_2") (pintype "passive"))
      (node (ref "S253") (pin "2") (pinfunction "2_2") (pintype "passive"))
      (node (ref "S265") (pin "1") (pinfunction "1_1") (pintype "passive"))
    )
    (net (code "13") (name "/col12") (class "Default")
      (node (ref "S212") (pin "2") (pinfunction "2_2") (pintype "passive"))
      (node (ref "S226") (pin "2") (pinfunction "2_2") (pintype "passive"))
      (node (ref "S240") (pin "2") (pinfunction "2_2") (pintype "passive"))
      (node (ref "S241") (pin "1") (pinfunction "1_1") (pintype "passive"))
      (node (ref "S254") (pin "2") (pinfunction "2_2") (pintype "passive"))
    )
    (net (code "14") (name "/col13") (class "Default")
      (node (ref "S213") (pin "2") (pinfunction "2_2") (pintype "passive"))
      (node (ref "S227") (pin "2") (pinfunction "2_2") (pintype "passive"))
      (node (ref "S228_2") (pin "2") (pinfunction "2_2") (pintype "passive"))
      (node (ref "S256") (pin "2") (pinfunction "2_2") (pintype "passive"))
      (node (ref "S266") (pin "2") (pinfunction "2_2") (pintype "passive"))
    )
    (net (code "15") (name "/col14") (class "Default")
      (node (ref "S214") (pin "2") (pinfunction "2_2") (pintype "passive"))
      (node (ref "S228") (pin "2") (pinfunction "2_2") (pintype "passive"))
      (node (ref "S242") (pin "2") (pinfunction "2_2") (pintype "passive"))
      (node (ref "S259") (pin "2") (pinfunction "2_2") (pintype "passive"))
      (node (ref "S269") (pin "2") (pinfunction "2_2") (pintype "passive"))
    )
    (net (code "16") (name "/row1") (class "Default")
      (node (ref "D201") (pin "2") (pinfunction "K_2") (pintype "passive"))
      (node (ref "D202") (pin "2") (pinfunction "K_2") (pintype "passive"))
      (node (ref "D203") (pin "2") (pinfunction "K_2") (pintype "passive"))
      (node (ref "D204") (pin "2") (pinfunction "K_2") (pintype "passive"))
      (node (ref "D205") (pin "2") (pinfunction "K_2") (pintype "passive"))
      (node (ref "D206") (pin "2") (pinfunction "K_2") (pintype "passive"))
      (node (ref "D207") (pin "2") (pinfunction "K_2") (pintype "passive"))
      (node (ref "D208") (pin "2") (pinfunction "K_2") (pintype "passive"))
      (node (ref "D209") (pin "2") (pinfunction "K_2") (pintype "passive"))
      (node (ref "D210") (pin "2") (pinfunction "K_2") (pintype "passive"))
      (node (ref "D211") (pin "2") (pinfunction "K_2") (pintype "passive"))
      (node (ref "D212") (pin "2") (pinfunction "K_2") (pintype "passive"))
      (node (ref "D213") (pin "2") (pinfunction "K_2") (pintype "passive"))
      (node (ref "D214") (pin "2") (pinfunction "K_2") (pintype "passive"))
    )
    (net (code "17") (name "/row2") (class "Default")
      (node (ref "D215") (pin "2") (pinfunction "K_2") (pintype "passive"))
      (node (ref "D216") (pin "2") (pinfunction "K_2") (pintype "passive"))
      (node (ref "D217") (pin "2") (pinfunction "K_2") (pintype "passive"))
      (node (ref "D218") (pin "2") (pinfunction "K_2") (pintype "passive"))
      (node (ref "D219") (pin "2") (pinfunction "K_2") (pintype "passive"))
      (node (ref "D220") (pin "2") (pinfunction "K_2") (pintype "passive"))
      (node (ref "D221") (pin "2") (pinfunction "K_2") (pintype "passive"))
      (node (ref "D222") (pin "2") (pinfunction "K_2") (pintype "passive"))
      (node (ref "D223") (pin "2") (pinfunction "K_2") (pintype "passive"))
      (node (ref "D224") (pin "2") (pinfunction "K_2") (pintype "passive"))
      (node (ref "D225") (pin "2") (pinfunction "K_2") (pintype "passive"))
      (node (ref "D226") (pin "2") (pinfunction "K_2") (pintype "passive"))
      (node (ref "D227") (pin "2") (pinfunction "K_2") (pintype "passive"))
      (node (ref "D228") (pin "2") (pinfunction "K_2") (pintype "passive"))
    )
    (net (code "18") (name "/row3") (class "Default")
      (node (ref "D228_2") (pin "2") (pinfunction "K_2") (pintype "passive"))
      (node (ref "D229") (pin "2") (pinfunction "K_2") (pintype "passive"))
      (node (ref "D230") (pin "2") (pinfunction "K_2") (pintype "passive"))
      (node (ref "D231") (pin "2") (pinfunction "K_2") (pintype "passive"))
      (node (ref "D232") (pin "2") (pinfunction "K_2") (pintype "passive"))
      (node (ref "D233") (pin "2") (pinfunction "K_2") (pintype "passive"))
      (node (ref "D234") (pin "2") (pinfunction "K_2") (pintype "passive"))
      (node (ref "D235") (pin "2") (pinfunction "K_2") (pintype "passive"))
      (node (ref "D236") (pin "2") (pinfunction "K_2") (pintype "passive"))
      (node (ref "D237") (pin "2") (pinfunction "K_2") (pintype "passive"))
      (node (ref "D238") (pin "2") (pinfunction "K_2") (pintype "passive"))
      (node (ref "D239") (pin "2") (pinfunction "K_2") (pintype "passive"))
      (node (ref "D240") (pin "2") (pinfunction "K_2") (pintype "passive"))
      (node (ref "D259") (pin "2") (pinfunction "K_2") (pintype "passive"))
    )
    (net (code "19") (name "/row4") (class "Default")
      (node (ref "D242") (pin "2") (pinfunction "K_2") (pintype "passive"))
      (node (ref "D243") (pin "2") (pinfunction "K_2") (pintype "passive"))
      (node (ref "D244") (pin "2") (pinfunction "K_2") (pintype "passive"))
      (node (ref "D245") (pin "2") (pinfunction "K_2") (pintype "passive"))
      (node (ref "D246") (pin "2") (pinfunction "K_2") (pintype "passive"))
      (node (ref "D247") (pin "2") (pinfunction "K_2") (pintype "passive"))
      (node (ref "D248") (pin "2") (pinfunction "K_2") (pintype "passive"))
      (node (ref "D249") (pin "2") (pinfunction "K_2") (pintype "passive"))
      (node (ref "D250") (pin "2") (pinfunction "K_2") (pintype "passive"))
      (node (ref "D251") (pin "2") (pinfunction "K_2") (pintype "passive"))
      (node (ref "D252") (pin "2") (pinfunction "K_2") (pintype "passive"))
      (node (ref "D253") (pin "2") (pinfunction "K_2") (pintype "passive"))
      (node (ref "D254") (pin "2") (pinfunction "K_2") (pintype "passive"))
      (node (ref "D255") (pin "2") (pinfunction "K_2") (pintype "passive"))
    )
    (net (code "20") (name "/row5") (class "Default")
      (node (ref "D241") (pin "2") (pinfunction "K_2") (pintype "passive"))
      (node (ref "D256") (pin "2") (pinfunction "K_2") (pintype "passive"))
      (node (ref "D257") (pin "2") (pinfunction "K_2") (pintype "passive"))
      (node (ref "D258") (pin "2") (pinfunction "K_2") (pintype "passive"))
      (node (ref "D260") (pin "2") (pinfunction "K_2") (pintype "passive"))
      (node (ref "D261") (pin "2") (pinfunction "K_2") (pintype "passive"))
      (node (ref "D262") (pin "2") (pinfunction "K_2") (pintype "passive"))
      (node (ref "D263") (pin "2") (pinfunction "K_2") (pintype "passive"))
      (node (ref "D264") (pin "2") (pinfunction "K_2") (pintype "passive"))
      (node (ref "D265") (pin "2") (pinfunction "K_2") (pintype "passive"))
      (node (ref "D266") (pin "2") (pinfunction "K_2") (pintype "passive"))
    )
    (net (code "21") (name "Net-(D201-A)") (class "Default")
      (node (ref "D201") (pin "1") (pinfunction "A_1") (pintype "passive"))
      (node (ref "S201") (pin "1") (pinfunction "1_1") (pintype "passive"))
    )
    (net (code "22") (name "Net-(D202-A)") (class "Default")
      (node (ref "D202") (pin "1") (pinfunction "A_1") (pintype "passive"))
      (node (ref "S202") (pin "1") (pinfunction "1_1") (pintype "passive"))
    )
    (net (code "23") (name "Net-(D203-A)") (class "Default")
      (node (ref "D203") (pin "1") (pinfunction "A_1") (pintype "passive"))
      (node (ref "S203") (pin "1") (pinfunction "1_1") (pintype "passive"))
    )
    (net (code "24") (name "Net-(D204-A)") (class "Default")
      (node (ref "D204") (pin "1") (pinfunction "A_1") (pintype "passive"))
      (node (ref "S204") (pin "1") (pinfunction "1_1") (pintype "passive"))
    )
    (net (code "25") (name "Net-(D205-A)") (class "Default")
      (node (ref "D205") (pin "1") (pinfunction "A_1") (pintype "passive"))
      (node (ref "S205") (pin "1") (pinfunction "1_1") (pintype "passive"))
    )
    (net (code "26") (name "Net-(D206-A)") (class "Default")
      (node (ref "D206") (pin "1") (pinfunction "A_1") (pintype "passive"))
      (node (ref "S206") (pin "1") (pinfunction "1_1") (pintype "passive"))
    )
    (net (code "27") (name "Net-(D207-A)") (class "Default")
      (node (ref "D207") (pin "1") (pinfunction "A_1") (pintype "passive"))
      (node (ref "S207") (pin "1") (pinfunction "1_1") (pintype "passive"))
    )
    (net (code "28") (name "Net-(D208-A)") (class "Default")
      (node (ref "D208") (pin "1") (pinfunction "A_1") (pintype "passive"))
      (node (ref "S208") (pin "1") (pinfunction "1_1") (pintype "passive"))
    )
    (net (code "29") (name "Net-(D209-A)") (class "Default")
      (node (ref "D209") (pin "1") (pinfunction "A_1") (pintype "passive"))
      (node (ref "S209") (pin "1") (pinfunction "1_1") (pintype "passive"))
    )
    (net (code "30") (name "Net-(D210-A)") (class "Default")
      (node (ref "D210") (pin "1") (pinfunction "A_1") (pintype "passive"))
      (node (ref "S210") (pin "1") (pinfunction "1_1") (pintype "passive"))
    )
    (net (code "31") (name "Net-(D211-A)") (class "Default")
      (node (ref "D211") (pin "1") (pinfunction "A_1") (pintype "passive"))
      (node (ref "S211") (pin "1") (pinfunction "1_1") (pintype "passive"))
    )
    (net (code "32") (name "Net-(D212-A)") (class "Default")
      (node (ref "D212") (pin "1") (pinfunction "A_1") (pintype "passive"))
      (node (ref "S212") (pin "1") (pinfunction "1_1") (pintype "passive"))
    )
    (net (code "33") (name "Net-(D213-A)") (class "Default")
      (node (ref "D213") (pin "1") (pinfunction "A_1") (pintype "passive"))
      (node (ref "S213") (pin "1") (pinfunction "1_1") (pintype "passive"))
    )
    (net (code "34") (name "Net-(D214-A)") (class "Default")
      (node (ref "D214") (pin "1") (pinfunction "A_1") (pintype "passive"))
      (node (ref "S214") (pin "1") (pinfunction "1_1") (pintype "passive"))
    )
    (net (code "35") (name "Net-(D215-A)") (class "Default")
      (node (ref "D215") (pin "1") (pinfunction "A_1") (pintype "passive"))
      (node (ref "S215") (pin "1") (pinfunction "1_1") (pintype "passive"))
    )
    (net (code "36") (name "Net-(D216-A)") (class "Default")
      (node (ref "D216") (pin "1") (pinfunction "A_1") (pintype "passive"))
      (node (ref "S216") (pin "1") (pinfunction "1_1") (pintype "passive"))
    )
    (net (code "37") (name "Net-(D217-A)") (class "Default")
      (node (ref "D217") (pin "1") (pinfunction "A_1") (pintype "passive"))
      (node (ref "S217") (pin "1") (pinfunction "1_1") (pintype "passive"))
    )
    (net (code "38") (name "Net-(D218-A)") (class "Default")
      (node (ref "D218") (pin "1") (pinfunction "A_1") (pintype "passive"))
      (node (ref "S218") (pin "1") (pinfunction "1_1") (pintype "passive"))
    )
    (net (code "39") (name "Net-(D219-A)") (class "Default")
      (node (ref "D219") (pin "1") (pinfunction "A_1") (pintype "passive"))
      (node (ref "S219") (pin "1") (pinfunction "1_1") (pintype "passive"))
    )
    (net (code "40") (name "Net-(D220-A)") (class "Default")
      (node (ref "D220") (pin "1") (pinfunction "A_1") (pintype "passive"))
      (node (ref "S220") (pin "1") (pinfunction "1_1") (pintype "passive"))
    )
    (net (code "41") (name "Net-(D221-A)") (class "Default")
      (node (ref "D221") (pin "1") (pinfunction "A_1") (pintype "passive"))
      (node (ref "S221") (pin "1") (pinfunction "1_1") (pintype "passive"))
    )
    (net (code "42") (name "Net-(D222-A)") (class "Default")
      (node (ref "D222") (pin "1") (pinfunction "A_1") (pintype "passive"))
      (node (ref "S222") (pin "1") (pinfunction "1_1") (pintype "passive"))
    )
    (net (code "43") (name "Net-(D223-A)") (class "Default")
      (node (ref "D223") (pin "1") (pinfunction "A_1") (pintype "passive"))
      (node (ref "S223") (pin "1") (pinfunction "1_1") (pintype "passive"))
    )
    (net (code "44") (name "Net-(D224-A)") (class "Default")
      (node (ref "D224") (pin "1") (pinfunction "A_1") (pintype "passive"))
      (node (ref "S224") (pin "1") (pinfunction "1_1") (pintype "passive"))
    )
    (net (code "45") (name "Net-(D225-A)") (class "Default")
      (node (ref "D225") (pin "1") (pinfunction "A_1") (pintype "passive"))
      (node (ref "S225") (pin "1") (pinfunction "1_1") (pintype "passive"))
    )
    (net (code "46") (name "Net-(D226-A)") (class "Default")
      (node (ref "D226") (pin "1") (pinfunction "A_1") (pintype "passive"))
      (node (ref "S226") (pin "1") (pinfunction "1_1") (pintype "passive"))
    )
    (net (code "47") (name "Net-(D227-A)") (class "Default")
      (node (ref "D227") (pin "1") (pinfunction "A_1") (pintype "passive"))
      (node (ref "S227") (pin "1") (pinfunction "1_1") (pintype "passive"))
    )
    (net (code "48") (name "Net-(D228-A)") (class "Default")
      (node (ref "D228") (pin "1") (pinfunction "A_1") (pintype "passive"))
      (node (ref "S228") (pin "1") (pinfunction "1_1") (pintype "passive"))
    )
    (net (code "49") (name "Net-(D228_2-A)") (class "Default")
      (node (ref "D228_2") (pin "1") (pinfunction "A_1") (pintype "passive"))
      (node (ref "S228_2") (pin "1") (pinfunction "1_1") (pintype "passive"))
    )
    (net (code "50") (name "Net-(D229-A)") (class "Default")
      (node (ref "D229") (pin "1") (pinfunction "A_1") (pintype "passive"))
      (node (ref "S229") (pin "2") (pinfunction "2_2") (pintype "passive"))
    )
    (net (code "51") (name "Net-(D230-A)") (class "Default")
      (node (ref "D230") (pin "1") (pinfunction "A_1") (pintype "passive"))
      (node (ref "S230") (pin "1") (pinfunction "1_1") (pintype "passive"))
    )
    (net (code "52") (name "Net-(D231-A)") (class "Default")
      (node (ref "D231") (pin "1") (pinfunction "A_1") (pintype "passive"))
      (node (ref "S231") (pin "1") (pinfunction "1_1") (pintype "passive"))
    )
    (net (code "53") (name "Net-(D232-A)") (class "Default")
      (node (ref "D232") (pin "1") (pinfunction "A_1") (pintype "passive"))
      (node (ref "S232") (pin "1") (pinfunction "1_1") (pintype "passive"))
    )
    (net (code "54") (name "Net-(D233-A)") (class "Default")
      (node (ref "D233") (pin "1") (pinfunction "A_1") (pintype "passive"))
      (node (ref "S233") (pin "1") (pinfunction "1_1") (pintype "passive"))
    )
    (net (code "55") (name "Net-(D234-A)") (class "Default")
      (node (ref "D234") (pin "1") (pinfunction "A_1") (pintype "passive"))
      (node (ref "S234") (pin "1") (pinfunction "1_1") (pintype "passive"))
    )
    (net (code "56") (name "Net-(D235-A)") (class "Default")
      (node (ref "D235") (pin "1") (pinfunction "A_1") (pintype "passive"))
      (node (ref "S235") (pin "1") (pinfunction "1_1") (pintype "passive"))
    )
    (net (code "57") (name "Net-(D236-A)") (class "Default")
      (node (ref "D236") (pin "1") (pinfunction "A_1") (pintype "passive"))
      (node (ref "S236") (pin "1") (pinfunction "1_1") (pintype "passive"))
    )
    (net (code "58") (name "Net-(D237-A)") (class "Default")
      (node (ref "D237") (pin "1") (pinfunction "A_1") (pintype "passive"))
      (node (ref "S237") (pin "1") (pinfunction "1_1") (pintype "passive"))
    )
    (net (code "59") (name "Net-(D238-A)") (class "Default")
      (node (ref "D238") (pin "1") (pinfunction "A_1") (pintype "passive"))
      (node (ref "S238") (pin "1") (pinfunction "1_1") (pintype "passive"))
    )
    (net (code "60") (name "Net-(D239-A)") (class "Default")
      (node (ref "D239") (pin "1") (pinfunction "A_1") (pintype "passive"))
      (node (ref "S239") (pin "1") (pinfunction "1_1") (pintype "passive"))
    )
    (net (code "61") (name "Net-(D240-A)") (class "Default")
      (node (ref "D240") (pin "1") (pinfunction "A_1") (pintype "passive"))
      (node (ref "S240") (pin "1") (pinfunction "1_1") (pintype "passive"))
    )
    (net (code "62") (name "Net-(D241-A)") (class "Default")
      (node (ref "D241") (pin "1") (pinfunction "A_1") (pintype "passive"))
      (node (ref "S241") (pin "2") (pinfunction "2_2") (pintype "passive"))
    )
    (net (code "63") (name "Net-(D242-A)") (class "Default")
      (node (ref "D242") (pin "1") (pinfunction "A_1") (pintype "passive"))
      (node (ref "S242") (pin "1") (pinfunction "1_1") (pintype "passive"))
    )
    (net (code "64") (name "Net-(D243-A)") (class "Default")
      (node (ref "D243") (pin "1") (pinfunction "A_1") (pintype "passive"))
      (node (ref "S243") (pin "1") (pinfunction "1_1") (pintype "passive"))
    )
    (net (code "65") (name "Net-(D244-A)") (class "Default")
      (node (ref "D244") (pin "1") (pinfunction "A_1") (pintype "passive"))
      (node (ref "S244") (pin "2") (pinfunction "2_2") (pintype "passive"))
    )
    (net (code "66") (name "Net-(D245-A)") (class "Default")
      (node (ref "D245") (pin "1") (pinfunction "A_1") (pintype "passive"))
      (node (ref "S245") (pin "1") (pinfunction "1_1") (pintype "passive"))
    )
    (net (code "67") (name "Net-(D246-A)") (class "Default")
      (node (ref "D246") (pin "1") (pinfunction "A_1") (pintype "passive"))
      (node (ref "S246") (pin "1") (pinfunction "1_1") (pintype "passive"))
    )
    (net (code "68") (name "Net-(D247-A)") (class "Default")
      (node (ref "D247") (pin "1") (pinfunction "A_1") (pintype "passive"))
      (node (ref "S247") (pin "1") (pinfunction "1_1") (pintype "passive"))
    )
    (net (code "69") (name "Net-(D248-A)") (class "Default")
      (node (ref "D248") (pin "1") (pinfunction "A_1") (pintype "passive"))
      (node (ref "S248") (pin "1") (pinfunction "1_1") (pintype "passive"))
    )
    (net (code "70") (name "Net-(D249-A)") (class "Default")
      (node (ref "D249") (pin "1") (pinfunction "A_1") (pintype "passive"))
      (node (ref "S249") (pin "1") (pinfunction "1_1") (pintype "passive"))
    )
    (net (code "71") (name "Net-(D250-A)") (class "Default")
      (node (ref "D250") (pin "1") (pinfunction "A_1") (pintype "passive"))
      (node (ref "S250") (pin "1") (pinfunction "1_1") (pintype "passive"))
    )
    (net (code "72") (name "Net-(D251-A)") (class "Default")
      (node (ref "D251") (pin "1") (pinfunction "A_1") (pintype "passive"))
      (node (ref "S251") (pin "1") (pinfunction "1_1") (pintype "passive"))
    )
    (net (code "73") (name "Net-(D252-A)") (class "Default")
      (node (ref "D252") (pin "1") (pinfunction "A_1") (pintype "passive"))
      (node (ref "S252") (pin "1") (pinfunction "1_1") (pintype "passive"))
    )
    (net (code "74") (name "Net-(D253-A)") (class "Default")
      (node (ref "D253") (pin "1") (pinfunction "A_1") (pintype "passive"))
      (node (ref "S253") (pin "1") (pinfunction "1_1") (pintype "passive"))
    )
    (net (code "75") (name "Net-(D254-A)") (class "Default")
      (node (ref "D254") (pin "1") (pinfunction "A_1") (pintype "passive"))
      (node (ref "S254") (pin "1") (pinfunction "1_1") (pintype "passive"))
    )
    (net (code "76") (name "Net-(D255-A)") (class "Default")
      (node (ref "D255") (pin "1") (pinfunction "A_1") (pintype "passive"))
      (node (ref "S256") (pin "1") (pinfunction "1_1") (pintype "passive"))
    )
    (net (code "77") (name "Net-(D256-A)") (class "Default")
      (node (ref "D256") (pin "1") (pinfunction "A_1") (pintype "passive"))
      (node (ref "S269") (pin "1") (pinfunction "1_1") (pintype "passive"))
    )
    (net (code "78") (name "Net-(D257-A)") (class "Default")
      (node (ref "D257") (pin "1") (pinfunction "A_1") (pintype "passive"))
      (node (ref "S257") (pin "2") (pinfunction "2_2") (pintype "passive"))
    )
    (net (code "79") (name "Net-(D258-A)") (class "Default")
      (node (ref "D258") (pin "1") (pinfunction "A_1") (pintype "passive"))
      (node (ref "S258") (pin "1") (pinfunction "1_1") (pintype "passive"))
    )
    (net (code "80") (name "Net-(D260-A)") (class "Default")
      (node (ref "D260") (pin "1") (pinfunction "A_1") (pintype "passive"))
      (node (ref "S260") (pin "1") (pinfunction "1_1") (pintype "passive"))
      (node (ref "S260_1") (pin "1") (pinfunction "1_1") (pintype "passive"))
    )
    (net (code "81") (name "Net-(D261-A)") (class "Default")
      (node (ref "D261") (pin "1") (pinfunction "A_1") (pintype "passive"))
      (node (ref "S261") (pin "1") (pinfunction "1_1") (pintype "passive"))
      (node (ref "S261_1") (pin "1") (pinfunction "1_1") (pintype "passive"))
      (node (ref "S261_2") (pin "1") (pinfunction "1_1") (pintype "passive"))
    )
    (net (code "82") (name "Net-(D262-A)") (class "Default")
      (node (ref "D262") (pin "1") (pinfunction "A_1") (pintype "passive"))
      (node (ref "S262") (pin "2") (pinfunction "2_2") (pintype "passive"))
      (node (ref "S262_1") (pin "2") (pinfunction "2_2") (pintype "passive"))
    )
    (net (code "83") (name "Net-(D263-A)") (class "Default")
      (node (ref "D263") (pin "1") (pinfunction "A_1") (pintype "passive"))
      (node (ref "S263") (pin "2") (pinfunction "2_2") (pintype "passive"))
      (node (ref "S263_1") (pin "2") (pinfunction "2_2") (pintype "passive"))
    )
    (net (code "84") (name "Net-(D264-A)") (class "Default")
      (node (ref "D264") (pin "1") (pinfunction "A_1") (pintype "passive"))
      (node (ref "S264") (pin "1") (pinfunction "1_1") (pintype "passive"))
    )
    (net (code "85") (name "Net-(D265-A)") (class "Default")
      (node (ref "D265") (pin "1") (pinfunction "A_1") (pintype "passive"))
      (node (ref "S265") (pin "2") (pinfunction "2_2") (pintype "passive"))
    )
    (net (code "86") (name "Net-(D266-A)") (class "Default")
      (node (ref "D266") (pin "1") (pinfunction "A_1") (pintype "passive"))
      (node (ref "S266") (pin "1") (pinfunction "1_1") (pintype "passive"))
    )
    (net (code "87") (name "unconnected-(STAB1-Pad1)") (class "Default")
      (node (ref "STAB1") (pin "1") (pinfunction "1_1") (pintype "passive"))
    )
  )
)
